# Spring2020V1_1.net
KiCad netlist of a schematic drawn in EAGLE
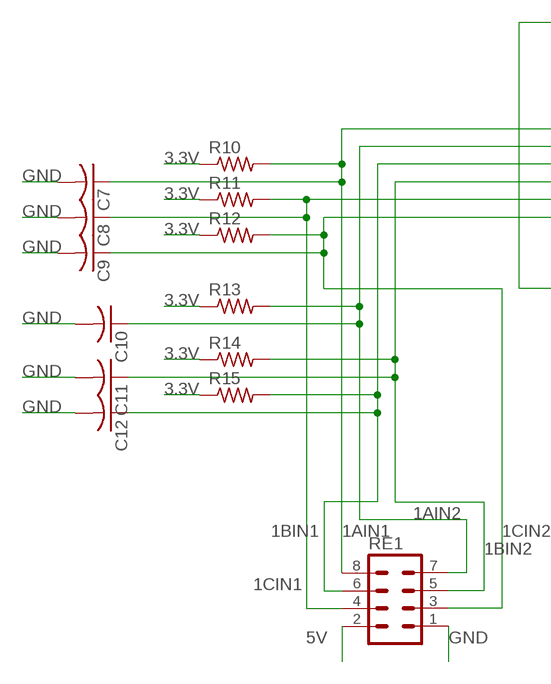
[diagram p0: schematic, sheet 1, part 1 of 2]
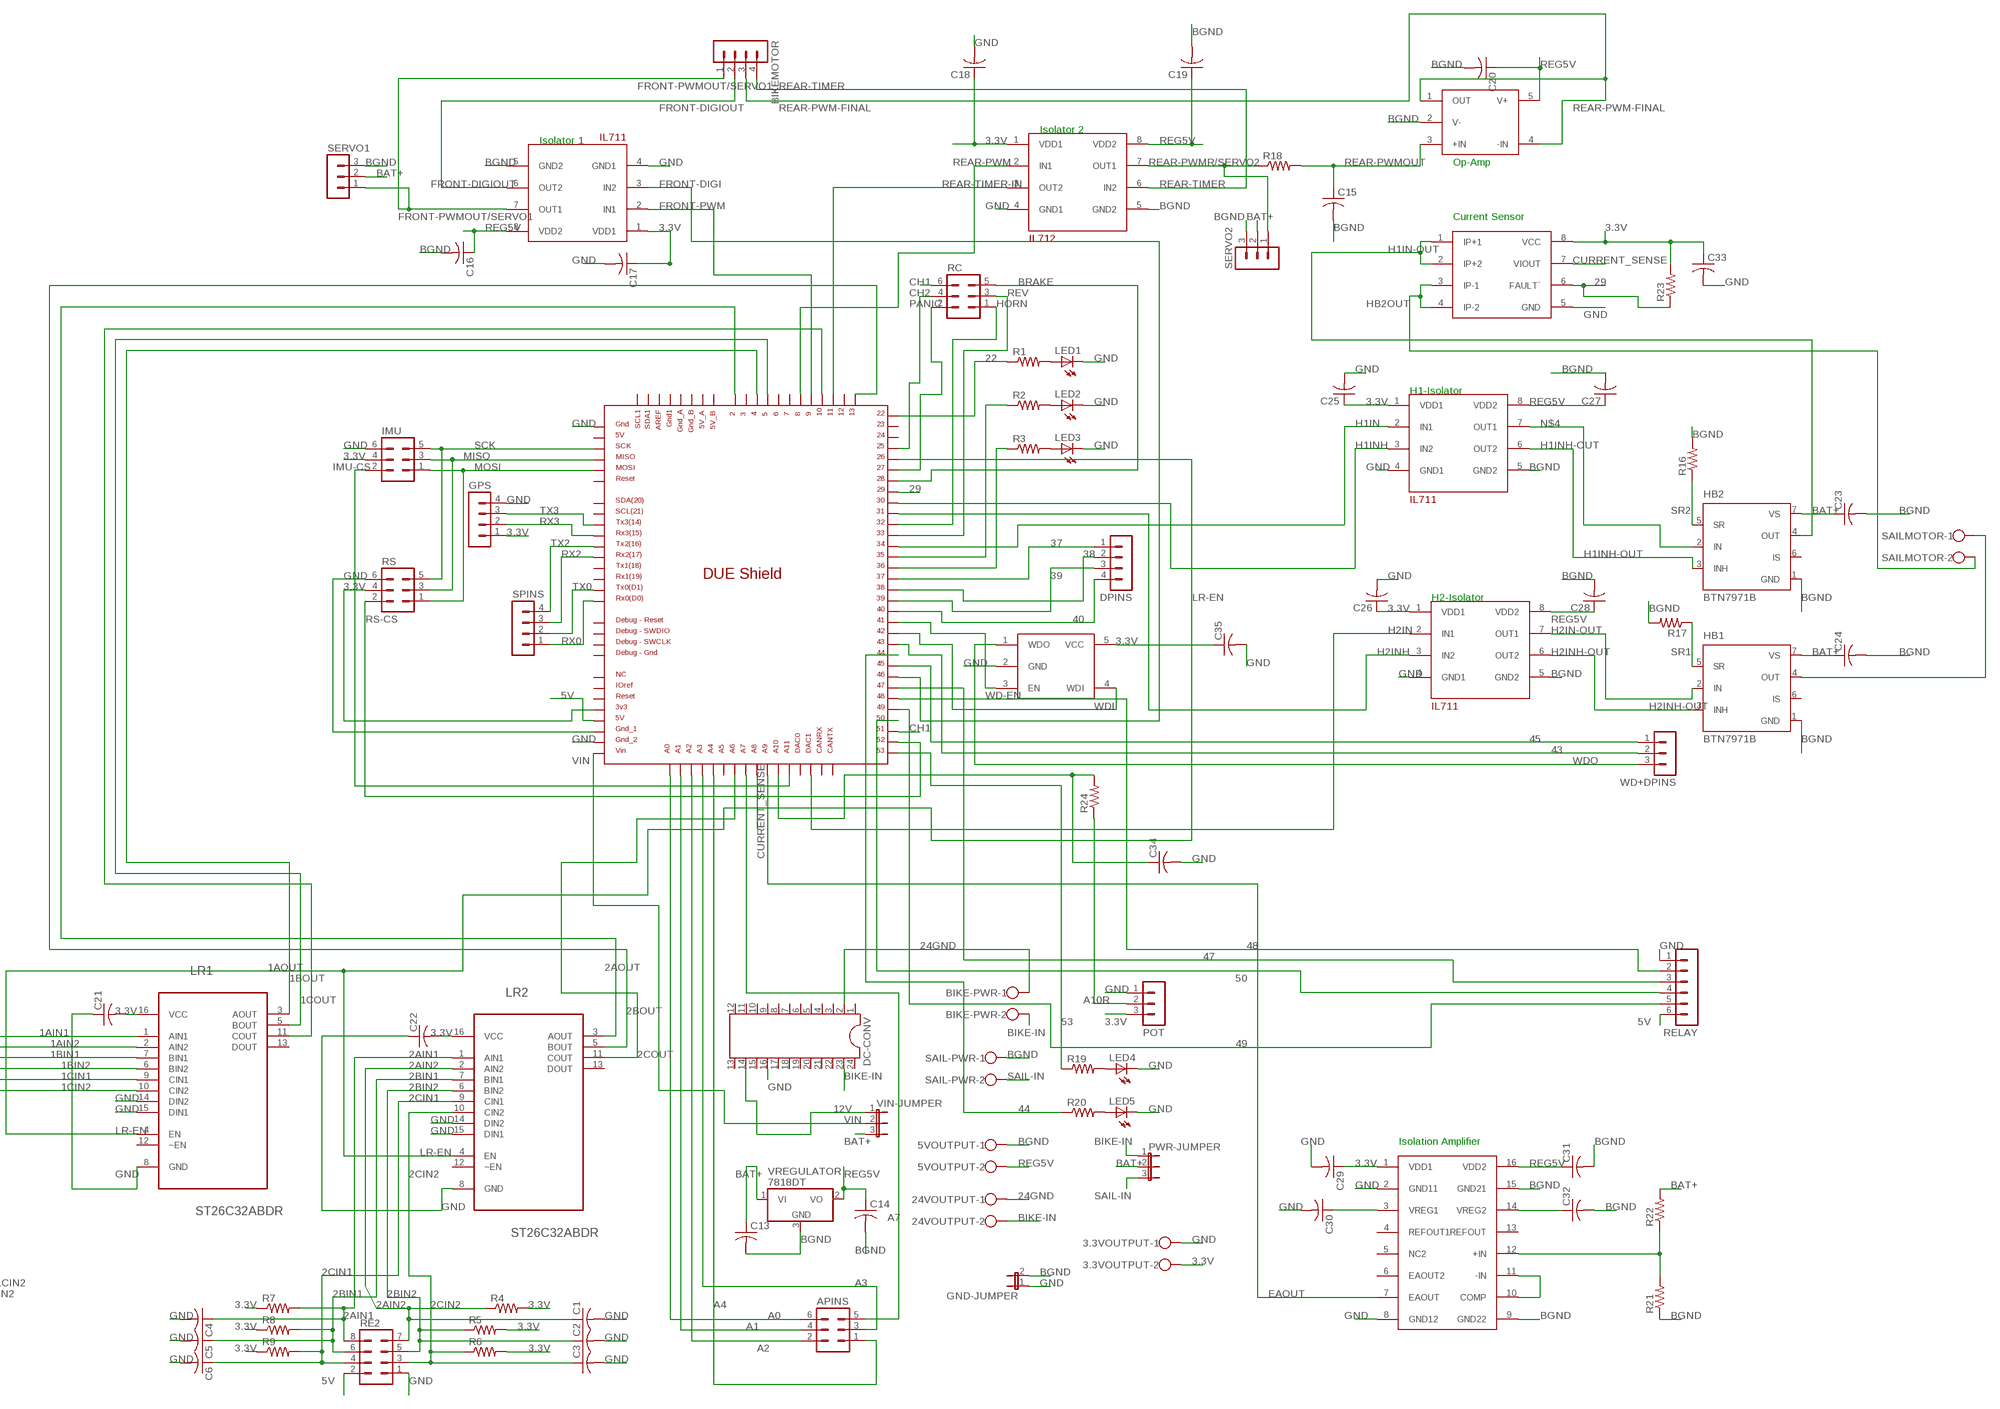
[diagram p1: schematic, sheet 1, part 2 of 2]

(export (version "E")
  (design (tool "Eeschema 10.0.6"))
  (components
    (comp (ref "3.3VOUTPUT")
      (value "W237-102")
      (footprint "eagle-import:W237-102")
      (fields (field (name "MPN") "237-102"))
      (libsource (lib "eagle-import") (part "W237-102"))
    )
    (comp (ref "5VOUTPUT")
      (value "W237-102")
      (footprint "eagle-import:W237-102")
      (fields (field (name "MPN") "237-102"))
      (libsource (lib "eagle-import") (part "W237-102"))
    )
    (comp (ref "24VOUTPUT")
      (value "W237-102")
      (footprint "eagle-import:W237-102")
      (fields (field (name "MPN") "237-102"))
      (libsource (lib "eagle-import") (part "W237-102"))
    )
    (comp (ref "APINS")
      (value "MA03-2")
      (footprint "eagle-import:MA03-2")
      (libsource (lib "eagle-import") (part "MA03-2"))
    )
    (comp (ref "BIKE-PWR")
      (value "W237-102")
      (footprint "eagle-import:W237-102")
      (fields (field (name "MPN") "237-102"))
      (libsource (lib "eagle-import") (part "W237-102"))
    )
    (comp (ref "BIKEMOTOR")
      (value "MA04-1")
      (footprint "eagle-import:MA04-1")
      (libsource (lib "eagle-import") (part "MA04-1"))
    )
    (comp (ref "C1")
      (value "C-US025-025X050")
      (footprint "eagle-import:C025-025X050")
      (libsource (lib "eagle-import") (part "C-US025-025X050"))
    )
    (comp (ref "C2")
      (value "C-US025-025X050")
      (footprint "eagle-import:C025-025X050")
      (libsource (lib "eagle-import") (part "C-US025-025X050"))
    )
    (comp (ref "C3")
      (value "C-US025-025X050")
      (footprint "eagle-import:C025-025X050")
      (libsource (lib "eagle-import") (part "C-US025-025X050"))
    )
    (comp (ref "C4")
      (value "C-US025-025X050")
      (footprint "eagle-import:C025-025X050")
      (libsource (lib "eagle-import") (part "C-US025-025X050"))
    )
    (comp (ref "C5")
      (value "C-US025-025X050")
      (footprint "eagle-import:C025-025X050")
      (libsource (lib "eagle-import") (part "C-US025-025X050"))
    )
    (comp (ref "C6")
      (value "C-US025-025X050")
      (footprint "eagle-import:C025-025X050")
      (libsource (lib "eagle-import") (part "C-US025-025X050"))
    )
    (comp (ref "C7")
      (value "C-US025-025X050")
      (footprint "eagle-import:C025-025X050")
      (libsource (lib "eagle-import") (part "C-US025-025X050"))
    )
    (comp (ref "C8")
      (value "C-US025-025X050")
      (footprint "eagle-import:C025-025X050")
      (libsource (lib "eagle-import") (part "C-US025-025X050"))
    )
    (comp (ref "C9")
      (value "C-US025-025X050")
      (footprint "eagle-import:C025-025X050")
      (libsource (lib "eagle-import") (part "C-US025-025X050"))
    )
    (comp (ref "C10")
      (value "C-US025-025X050")
      (footprint "eagle-import:C025-025X050")
      (libsource (lib "eagle-import") (part "C-US025-025X050"))
    )
    (comp (ref "C11")
      (value "C-US025-025X050")
      (footprint "eagle-import:C025-025X050")
      (libsource (lib "eagle-import") (part "C-US025-025X050"))
    )
    (comp (ref "C12")
      (value "C-US025-025X050")
      (footprint "eagle-import:C025-025X050")
      (libsource (lib "eagle-import") (part "C-US025-025X050"))
    )
    (comp (ref "C13")
      (value "C-US025-050X050")
      (footprint "eagle-import:C025-050X050")
      (libsource (lib "eagle-import") (part "C-US025-050X050"))
    )
    (comp (ref "C14")
      (value "C-US025-050X050")
      (footprint "eagle-import:C025-050X050")
      (libsource (lib "eagle-import") (part "C-US025-050X050"))
    )
    (comp (ref "C15")
      (value "C-US025-050X050")
      (footprint "eagle-import:C025-050X050")
      (libsource (lib "eagle-import") (part "C-US025-050X050"))
    )
    (comp (ref "C16")
      (value "C-US025-050X050")
      (footprint "eagle-import:C025-050X050")
      (libsource (lib "eagle-import") (part "C-US025-050X050"))
    )
    (comp (ref "C17")
      (value "C-US025-050X050")
      (footprint "eagle-import:C025-050X050")
      (libsource (lib "eagle-import") (part "C-US025-050X050"))
    )
    (comp (ref "C18")
      (value "C-US025-050X050")
      (footprint "eagle-import:C025-050X050")
      (libsource (lib "eagle-import") (part "C-US025-050X050"))
    )
    (comp (ref "C19")
      (value "C-US025-050X050")
      (footprint "eagle-import:C025-050X050")
      (libsource (lib "eagle-import") (part "C-US025-050X050"))
    )
    (comp (ref "C20")
      (value "C-US025-050X050")
      (footprint "eagle-import:C025-050X050")
      (libsource (lib "eagle-import") (part "C-US025-050X050"))
    )
    (comp (ref "C21")
      (value "C-US025-050X050")
      (footprint "eagle-import:C025-050X050")
      (libsource (lib "eagle-import") (part "C-US025-050X050"))
    )
    (comp (ref "C22")
      (value "C-US025-050X050")
      (footprint "eagle-import:C025-050X050")
      (libsource (lib "eagle-import") (part "C-US025-050X050"))
    )
    (comp (ref "C23")
      (value "C-US150-091X182")
      (footprint "eagle-import:C150-091X182")
      (libsource (lib "eagle-import") (part "C-US150-091X182"))
    )
    (comp (ref "C24")
      (value "C-US150-091X182")
      (footprint "eagle-import:C150-091X182")
      (libsource (lib "eagle-import") (part "C-US150-091X182"))
    )
    (comp (ref "C25")
      (value "C-US025-050X050")
      (footprint "eagle-import:C025-050X050")
      (libsource (lib "eagle-import") (part "C-US025-050X050"))
    )
    (comp (ref "C26")
      (value "C-US025-050X050")
      (footprint "eagle-import:C025-050X050")
      (libsource (lib "eagle-import") (part "C-US025-050X050"))
    )
    (comp (ref "C27")
      (value "C-US025-050X050")
      (footprint "eagle-import:C025-050X050")
      (libsource (lib "eagle-import") (part "C-US025-050X050"))
    )
    (comp (ref "C28")
      (value "C-US025-050X050")
      (footprint "eagle-import:C025-050X050")
      (libsource (lib "eagle-import") (part "C-US025-050X050"))
    )
    (comp (ref "C29")
      (value "C-US025-050X050")
      (footprint "eagle-import:C025-050X050")
      (libsource (lib "eagle-import") (part "C-US025-050X050"))
    )
    (comp (ref "C30")
      (value "C-US025-050X050")
      (footprint "eagle-import:C025-050X050")
      (libsource (lib "eagle-import") (part "C-US025-050X050"))
    )
    (comp (ref "C31")
      (value "C-US025-050X050")
      (footprint "eagle-import:C025-050X050")
      (libsource (lib "eagle-import") (part "C-US025-050X050"))
    )
    (comp (ref "C32")
      (value "C-US025-050X050")
      (footprint "eagle-import:C025-050X050")
      (libsource (lib "eagle-import") (part "C-US025-050X050"))
    )
    (comp (ref "C33")
      (value "C-US025-050X050")
      (footprint "eagle-import:C025-050X050")
      (libsource (lib "eagle-import") (part "C-US025-050X050"))
    )
    (comp (ref "C34")
      (value "C-US025-050X050")
      (footprint "eagle-import:C025-050X050")
      (libsource (lib "eagle-import") (part "C-US025-050X050"))
    )
    (comp (ref "C35")
      (value "C-US025-025X050")
      (footprint "eagle-import:C025-025X050")
      (libsource (lib "eagle-import") (part "C-US025-025X050"))
    )
    (comp (ref "DC-CONV")
      (value "CU.INC---VAWQ6-Q48-S12H-6")
      (footprint "eagle-import:DIL24-6")
      (libsource (lib "eagle-import") (part "CU.INC---VAWQ6-Q48-S12H-6"))
    )
    (comp (ref "DPINS")
      (value "MA04-1")
      (footprint "eagle-import:MA04-1")
      (libsource (lib "eagle-import") (part "MA04-1"))
    )
    (comp (ref "GND-JUMPER")
      (value "JP1E")
      (footprint "eagle-import:JP1")
      (libsource (lib "eagle-import") (part "JP1E"))
    )
    (comp (ref "GPS")
      (value "MA04-1")
      (footprint "eagle-import:MA04-1")
      (libsource (lib "eagle-import") (part "MA04-1"))
    )
    (comp (ref "HB1")
      (value "BTN7971B")
      (footprint "eagle-import:P-TO263-7-1")
      (libsource (lib "eagle-import") (part "BTN7971B"))
    )
    (comp (ref "HB2")
      (value "BTN7971B")
      (footprint "eagle-import:P-TO263-7-1")
      (libsource (lib "eagle-import") (part "BTN7971B"))
    )
    (comp (ref "IMU")
      (value "MA03-2")
      (footprint "eagle-import:MA03-2")
      (libsource (lib "eagle-import") (part "MA03-2"))
    )
    (comp (ref "LED1")
      (value "LED5MM")
      (footprint "eagle-import:LED5MM")
      (libsource (lib "eagle-import") (part "LED5MM"))
    )
    (comp (ref "LED2")
      (value "LED5MM")
      (footprint "eagle-import:LED5MM")
      (libsource (lib "eagle-import") (part "LED5MM"))
    )
    (comp (ref "LED3")
      (value "LED5MM")
      (footprint "eagle-import:LED5MM")
      (libsource (lib "eagle-import") (part "LED5MM"))
    )
    (comp (ref "LED4")
      (value "LED5MM")
      (footprint "eagle-import:LED5MM")
      (libsource (lib "eagle-import") (part "LED5MM"))
    )
    (comp (ref "LED5")
      (value "LED5MM")
      (footprint "eagle-import:LED5MM")
      (libsource (lib "eagle-import") (part "LED5MM"))
    )
    (comp (ref "LR1")
      (value "ST26C32ABDR")
      (footprint "eagle-import:SOIC127P600X175-16N")
      (libsource (lib "eagle-import") (part "ST26C32ABDR"))
    )
    (comp (ref "LR2")
      (value "ST26C32ABDR")
      (footprint "eagle-import:SOIC127P600X175-16N")
      (libsource (lib "eagle-import") (part "ST26C32ABDR"))
    )
    (comp (ref "OP-AMP")
      (value "OPAMP")
      (footprint "eagle-import:SOT95P280X145-5N")
      (libsource (lib "eagle-import") (part "OPAMP"))
    )
    (comp (ref "POT")
      (value "MA03-1")
      (footprint "eagle-import:MA03-1")
      (libsource (lib "eagle-import") (part "MA03-1"))
    )
    (comp (ref "PWR-JUMPER")
      (value "JP2E")
      (footprint "eagle-import:JP2")
      (libsource (lib "eagle-import") (part "JP2E"))
    )
    (comp (ref "R1")
      (value "R-US_0309/10")
      (footprint "eagle-import:0309_10")
      (libsource (lib "eagle-import") (part "R-US_0309/10"))
    )
    (comp (ref "R2")
      (value "R-US_0309/10")
      (footprint "eagle-import:0309_10")
      (libsource (lib "eagle-import") (part "R-US_0309/10"))
    )
    (comp (ref "R3")
      (value "R-US_0309/10")
      (footprint "eagle-import:0309_10")
      (libsource (lib "eagle-import") (part "R-US_0309/10"))
    )
    (comp (ref "R4")
      (value "R-US_0613/15")
      (footprint "eagle-import:P0613_15")
      (libsource (lib "eagle-import") (part "resistor_R-US_0613/15"))
    )
    (comp (ref "R5")
      (value "R-US_0613/15")
      (footprint "eagle-import:P0613_15")
      (libsource (lib "eagle-import") (part "resistor_R-US_0613/15"))
    )
    (comp (ref "R6")
      (value "R-US_0613/15")
      (footprint "eagle-import:P0613_15")
      (libsource (lib "eagle-import") (part "resistor_R-US_0613/15"))
    )
    (comp (ref "R7")
      (value "R-US_0613/15")
      (footprint "eagle-import:P0613_15")
      (libsource (lib "eagle-import") (part "resistor_R-US_0613/15"))
    )
    (comp (ref "R8")
      (value "R-US_0613/15")
      (footprint "eagle-import:P0613_15")
      (libsource (lib "eagle-import") (part "resistor_R-US_0613/15"))
    )
    (comp (ref "R9")
      (value "R-US_0613/15")
      (footprint "eagle-import:P0613_15")
      (libsource (lib "eagle-import") (part "resistor_R-US_0613/15"))
    )
    (comp (ref "R10")
      (value "R-US_0613/15")
      (footprint "eagle-import:P0613_15")
      (libsource (lib "eagle-import") (part "resistor_R-US_0613/15"))
    )
    (comp (ref "R11")
      (value "R-US_0613/15")
      (footprint "eagle-import:P0613_15")
      (libsource (lib "eagle-import") (part "resistor_R-US_0613/15"))
    )
    (comp (ref "R12")
      (value "R-US_0613/15")
      (footprint "eagle-import:P0613_15")
      (libsource (lib "eagle-import") (part "resistor_R-US_0613/15"))
    )
    (comp (ref "R13")
      (value "R-US_0613/15")
      (footprint "eagle-import:P0613_15")
      (libsource (lib "eagle-import") (part "resistor_R-US_0613/15"))
    )
    (comp (ref "R14")
      (value "R-US_0613/15")
      (footprint "eagle-import:P0613_15")
      (libsource (lib "eagle-import") (part "resistor_R-US_0613/15"))
    )
    (comp (ref "R15")
      (value "R-US_0613/15")
      (footprint "eagle-import:P0613_15")
      (libsource (lib "eagle-import") (part "resistor_R-US_0613/15"))
    )
    (comp (ref "R16")
      (value "R-US_0613/15")
      (footprint "eagle-import:P0613_15")
      (libsource (lib "eagle-import") (part "resistor_R-US_0613/15"))
    )
    (comp (ref "R17")
      (value "R-US_0613/15")
      (footprint "eagle-import:P0613_15")
      (libsource (lib "eagle-import") (part "resistor_R-US_0613/15"))
    )
    (comp (ref "R18")
      (value "R-US_0414/15")
      (footprint "eagle-import:0414_15")
      (libsource (lib "eagle-import") (part "resistor_R-US_0414/15"))
    )
    (comp (ref "R19")
      (value "R-US_0309/10")
      (footprint "eagle-import:0309_10")
      (libsource (lib "eagle-import") (part "R-US_0309/10"))
    )
    (comp (ref "R20")
      (value "R-US_0309/10")
      (footprint "eagle-import:0309_10")
      (libsource (lib "eagle-import") (part "R-US_0309/10"))
    )
    (comp (ref "R21")
      (value "R-US_0414/15")
      (footprint "eagle-import:0414_15")
      (libsource (lib "eagle-import") (part "resistor_R-US_0414/15"))
    )
    (comp (ref "R22")
      (value "R-US_0414/15")
      (footprint "eagle-import:0414_15")
      (libsource (lib "eagle-import") (part "resistor_R-US_0414/15"))
    )
    (comp (ref "R23")
      (value "R-US_0414/15")
      (footprint "eagle-import:0414_15")
      (libsource (lib "eagle-import") (part "resistor_R-US_0414/15"))
    )
    (comp (ref "R24")
      (value "R-US_0414/15")
      (footprint "eagle-import:0414_15")
      (libsource (lib "eagle-import") (part "resistor_R-US_0414/15"))
    )
    (comp (ref "RC")
      (value "MA03-2")
      (footprint "eagle-import:MA03-2")
      (libsource (lib "eagle-import") (part "MA03-2"))
    )
    (comp (ref "RE1")
      (value "MA04-2")
      (footprint "eagle-import:MA04-2")
      (libsource (lib "eagle-import") (part "MA04-2"))
    )
    (comp (ref "RE2")
      (value "MA04-2")
      (footprint "eagle-import:MA04-2")
      (libsource (lib "eagle-import") (part "MA04-2"))
    )
    (comp (ref "RELAY")
      (value "MA06-1")
      (footprint "eagle-import:MA06-1")
      (libsource (lib "eagle-import") (part "MA06-1"))
    )
    (comp (ref "RS")
      (value "MA03-2")
      (footprint "eagle-import:MA03-2")
      (libsource (lib "eagle-import") (part "MA03-2"))
    )
    (comp (ref "SAIL-PWR")
      (value "W237-102")
      (footprint "eagle-import:W237-102")
      (fields (field (name "MPN") "237-102"))
      (libsource (lib "eagle-import") (part "W237-102"))
    )
    (comp (ref "SAILMOTOR")
      (value "W237-102")
      (footprint "eagle-import:W237-102")
      (fields (field (name "MPN") "237-102"))
      (libsource (lib "eagle-import") (part "W237-102"))
    )
    (comp (ref "SERVO1")
      (value "MA03-1")
      (footprint "eagle-import:MA03-1")
      (libsource (lib "eagle-import") (part "MA03-1"))
    )
    (comp (ref "SERVO2")
      (value "MA03-1")
      (footprint "eagle-import:MA03-1")
      (libsource (lib "eagle-import") (part "MA03-1"))
    )
    (comp (ref "SPINS")
      (value "MA04-1")
      (footprint "eagle-import:MA04-1")
      (libsource (lib "eagle-import") (part "MA04-1"))
    )
    (comp (ref "U$1")
      (value "DUE(NORMAL)")
      (footprint "eagle-import:DUE(NORMAL)")
      (libsource (lib "eagle-import") (part "DUE(NORMAL)"))
    )
    (comp (ref "U$2")
      (value "IL-711")
      (footprint "eagle-import:8PINSOIC")
      (libsource (lib "eagle-import") (part "IL-711"))
    )
    (comp (ref "U$3")
      (value "IL-711")
      (footprint "eagle-import:8PINSOIC")
      (libsource (lib "eagle-import") (part "IL-711"))
    )
    (comp (ref "U$4")
      (value "WATCHDOG")
      (footprint "eagle-import:SOT95P280X145-5N")
      (libsource (lib "eagle-import") (part "WATCHDOG"))
    )
    (comp (ref "U$5")
      (value "ISOLATED_ERROR_AMP_ADUM3190")
      (footprint "eagle-import:QSOP16")
      (libsource (lib "eagle-import") (part "ISOLATED_ERROR_AMP_ADUM3190"))
    )
    (comp (ref "U$6")
      (value "IL-711")
      (footprint "eagle-import:8PINSOIC")
      (libsource (lib "eagle-import") (part "IL-711"))
    )
    (comp (ref "U$7")
      (value "IL-712")
      (footprint "eagle-import:8PINSOIC")
      (libsource (lib "eagle-import") (part "IL-712"))
    )
    (comp (ref "U$8")
      (value "LINEAR_CURRENT_SENSOR_ACS711")
      (footprint "eagle-import:SO8")
      (libsource (lib "eagle-import") (part "LINEAR_CURRENT_SENSOR_ACS711"))
    )
    (comp (ref "VIN-JUMPER")
      (value "JP2E")
      (footprint "eagle-import:JP2")
      (libsource (lib "eagle-import") (part "JP2E"))
    )
    (comp (ref "VREGULATOR")
      (value "7818DT")
      (footprint "eagle-import:TO252")
      (libsource (lib "eagle-import") (part "78DT18"))
    )
    (comp (ref "WD+DPINS")
      (value "MA03-1")
      (footprint "eagle-import:MA03-1")
      (libsource (lib "eagle-import") (part "MA03-1"))
    )
  )
  (nets
    (net (code "1") (name "/1AIN1") (class "Default")
      (node (ref "C7") (pin "1") (pinfunction "1_1") (pintype "passive"))
      (node (ref "LR1") (pin "1") (pinfunction "AIN1_1") (pintype "input"))
      (node (ref "R10") (pin "2") (pinfunction "2_2") (pintype "passive"))
      (node (ref "RE1") (pin "8") (pinfunction "8_8") (pintype "passive"))
    )
    (net (code "2") (name "/1AIN2") (class "Default")
      (node (ref "C10") (pin "1") (pinfunction "1_1") (pintype "passive"))
      (node (ref "LR1") (pin "2") (pinfunction "AIN2_2") (pintype "input"))
      (node (ref "R13") (pin "2") (pinfunction "2_2") (pintype "passive"))
      (node (ref "RE1") (pin "7") (pinfunction "7_7") (pintype "passive"))
    )
    (net (code "3") (name "/1AOUT") (class "Default")
      (node (ref "LR1") (pin "3") (pinfunction "AOUT_3") (pintype "output"))
      (node (ref "U$1") (pin "4") (pinfunction "4_4") (pintype "bidirectional"))
    )
    (net (code "4") (name "/1BIN1") (class "Default")
      (node (ref "C12") (pin "1") (pinfunction "1_1") (pintype "passive"))
      (node (ref "LR1") (pin "7") (pinfunction "BIN1_7") (pintype "input"))
      (node (ref "R15") (pin "2") (pinfunction "2_2") (pintype "passive"))
      (node (ref "RE1") (pin "6") (pinfunction "6_6") (pintype "passive"))
    )
    (net (code "5") (name "/1BIN2") (class "Default")
      (node (ref "C11") (pin "1") (pinfunction "1_1") (pintype "passive"))
      (node (ref "LR1") (pin "6") (pinfunction "BIN2_6") (pintype "input"))
      (node (ref "R14") (pin "2") (pinfunction "2_2") (pintype "passive"))
      (node (ref "RE1") (pin "5") (pinfunction "5_5") (pintype "passive"))
    )
    (net (code "6") (name "/1BOUT") (class "Default")
      (node (ref "LR1") (pin "5") (pinfunction "BOUT_5") (pintype "output"))
      (node (ref "U$1") (pin "5") (pinfunction "5_5") (pintype "bidirectional"))
    )
    (net (code "7") (name "/1CIN1") (class "Default")
      (node (ref "C8") (pin "1") (pinfunction "1_1") (pintype "passive"))
      (node (ref "LR1") (pin "9") (pinfunction "CIN1_9") (pintype "input"))
      (node (ref "R11") (pin "2") (pinfunction "2_2") (pintype "passive"))
      (node (ref "RE1") (pin "4") (pinfunction "4_4") (pintype "passive"))
    )
    (net (code "8") (name "/1CIN2") (class "Default")
      (node (ref "C9") (pin "1") (pinfunction "1_1") (pintype "passive"))
      (node (ref "LR1") (pin "10") (pinfunction "CIN2_10") (pintype "input"))
      (node (ref "R12") (pin "2") (pinfunction "2_2") (pintype "passive"))
      (node (ref "RE1") (pin "3") (pinfunction "3_3") (pintype "passive"))
    )
    (net (code "9") (name "/1COUT") (class "Default")
      (node (ref "LR1") (pin "11") (pinfunction "COUT_11") (pintype "output"))
      (node (ref "U$1") (pin "10") (pinfunction "10_10") (pintype "bidirectional"))
    )
    (net (code "10") (name "/2AIN1") (class "Default")
      (node (ref "C4") (pin "1") (pinfunction "1_1") (pintype "passive"))
      (node (ref "LR2") (pin "1") (pinfunction "AIN1_1") (pintype "input"))
      (node (ref "R7") (pin "2") (pinfunction "2_2") (pintype "passive"))
      (node (ref "RE2") (pin "8") (pinfunction "8_8") (pintype "passive"))
    )
    (net (code "11") (name "/2AIN2") (class "Default")
      (node (ref "C1") (pin "1") (pinfunction "1_1") (pintype "passive"))
      (node (ref "LR2") (pin "2") (pinfunction "AIN2_2") (pintype "input"))
      (node (ref "R4") (pin "1") (pinfunction "1_1") (pintype "passive"))
      (node (ref "RE2") (pin "7") (pinfunction "7_7") (pintype "passive"))
    )
    (net (code "12") (name "/2AOUT") (class "Default")
      (node (ref "LR2") (pin "3") (pinfunction "AOUT_3") (pintype "output"))
      (node (ref "U$1") (pin "2") (pinfunction "2_2") (pintype "bidirectional"))
    )
    (net (code "13") (name "/2BIN1") (class "Default")
      (node (ref "C5") (pin "1") (pinfunction "1_1") (pintype "passive"))
      (node (ref "LR2") (pin "7") (pinfunction "BIN1_7") (pintype "input"))
      (node (ref "R8") (pin "2") (pinfunction "2_2") (pintype "passive"))
      (node (ref "RE2") (pin "6") (pinfunction "6_6") (pintype "passive"))
    )
    (net (code "14") (name "/2BIN2") (class "Default")
      (node (ref "C2") (pin "1") (pinfunction "1_1") (pintype "passive"))
      (node (ref "LR2") (pin "6") (pinfunction "BIN2_6") (pintype "input"))
      (node (ref "R5") (pin "1") (pinfunction "1_1") (pintype "passive"))
      (node (ref "RE2") (pin "5") (pinfunction "5_5") (pintype "passive"))
    )
    (net (code "15") (name "/2BOUT") (class "Default")
      (node (ref "LR2") (pin "5") (pinfunction "BOUT_5") (pintype "output"))
      (node (ref "U$1") (pin "13") (pinfunction "13_13") (pintype "bidirectional"))
    )
    (net (code "16") (name "/2CIN1") (class "Default")
      (node (ref "C6") (pin "1") (pinfunction "1_1") (pintype "passive"))
      (node (ref "LR2") (pin "9") (pinfunction "CIN1_9") (pintype "input"))
      (node (ref "R9") (pin "2") (pinfunction "2_2") (pintype "passive"))
      (node (ref "RE2") (pin "4") (pinfunction "4_4") (pintype "passive"))
    )
    (net (code "17") (name "/2CIN2") (class "Default")
      (node (ref "C3") (pin "1") (pinfunction "1_1") (pintype "passive"))
      (node (ref "LR2") (pin "10") (pinfunction "CIN2_10") (pintype "input"))
      (node (ref "R6") (pin "1") (pinfunction "1_1") (pintype "passive"))
      (node (ref "RE2") (pin "3") (pinfunction "3_3") (pintype "passive"))
    )
    (net (code "18") (name "/2COUT") (class "Default")
      (node (ref "LR2") (pin "11") (pinfunction "COUT_11") (pintype "output"))
      (node (ref "U$1") (pin "A6") (pinfunction "A6_A6") (pintype "bidirectional"))
    )
    (net (code "19") (name "/3.3V") (class "Default")
      (node (ref "3.3VOUTPUT") (pin "2") (pinfunction "KL_2") (pintype "passive"))
      (node (ref "C17") (pin "1") (pinfunction "1_1") (pintype "passive"))
      (node (ref "C18") (pin "1") (pinfunction "1_1") (pintype "passive"))
      (node (ref "C21") (pin "2") (pinfunction "2_2") (pintype "passive"))
      (node (ref "C22") (pin "2") (pinfunction "2_2") (pintype "passive"))
      (node (ref "C25") (pin "1") (pinfunction "1_1") (pintype "passive"))
      (node (ref "C26") (pin "1") (pinfunction "1_1") (pintype "passive"))
      (node (ref "C29") (pin "1") (pinfunction "1_1") (pintype "passive"))
      (node (ref "C33") (pin "1") (pinfunction "1_1") (pintype "passive"))
      (node (ref "C35") (pin "1") (pinfunction "1_1") (pintype "passive"))
      (node (ref "GPS") (pin "1") (pinfunction "1_1") (pintype "passive"))
      (node (ref "IMU") (pin "4") (pinfunction "4_4") (pintype "passive"))
      (node (ref "LR1") (pin "16") (pinfunction "VCC_16") (pintype "power_in"))
      (node (ref "LR2") (pin "16") (pinfunction "VCC_16") (pintype "power_in"))
      (node (ref "POT") (pin "3") (pinfunction "3_3") (pintype "passive"))
      (node (ref "R10") (pin "1") (pinfunction "1_1") (pintype "passive"))
      (node (ref "R11") (pin "1") (pinfunction "1_1") (pintype "passive"))
      (node (ref "R12") (pin "1") (pinfunction "1_1") (pintype "passive"))
      (node (ref "R13") (pin "1") (pinfunction "1_1") (pintype "passive"))
      (node (ref "R14") (pin "1") (pinfunction "1_1") (pintype "passive"))
      (node (ref "R15") (pin "1") (pinfunction "1_1") (pintype "passive"))
      (node (ref "R23") (pin "2") (pinfunction "2_2") (pintype "passive"))
      (node (ref "R4") (pin "2") (pinfunction "2_2") (pintype "passive"))
      (node (ref "R5") (pin "2") (pinfunction "2_2") (pintype "passive"))
      (node (ref "R6") (pin "2") (pinfunction "2_2") (pintype "passive"))
      (node (ref "R7") (pin "1") (pinfunction "1_1") (pintype "passive"))
      (node (ref "R8") (pin "1") (pinfunction "1_1") (pintype "passive"))
      (node (ref "R9") (pin "1") (pinfunction "1_1") (pintype "passive"))
      (node (ref "RS") (pin "4") (pinfunction "4_4") (pintype "passive"))
      (node (ref "U$1") (pin "3V3") (pinfunction "3V3_3V3") (pintype "bidirectional"))
      (node (ref "U$2") (pin "1") (pinfunction "VDD1_1") (pintype "power_in"))
      (node (ref "U$3") (pin "1") (pinfunction "VDD1_1") (pintype "power_in"))
      (node (ref "U$4") (pin "5") (pinfunction "VCC_5") (pintype "power_in"))
      (node (ref "U$5") (pin "1") (pinfunction "VDD1_1") (pintype "bidirectional"))
      (node (ref "U$6") (pin "1") (pinfunction "VDD1_1") (pintype "power_in"))
      (node (ref "U$7") (pin "1") (pinfunction "VDD1_1") (pintype "power_in"))
      (node (ref "U$8") (pin "8") (pinfunction "VCC_8") (pintype "bidirectional"))
    )
    (net (code "20") (name "/5V") (class "Default")
      (node (ref "RE1") (pin "2") (pinfunction "2_2") (pintype "passive"))
      (node (ref "RE2") (pin "2") (pinfunction "2_2") (pintype "passive"))
      (node (ref "RELAY") (pin "6") (pinfunction "6_6") (pintype "passive"))
      (node (ref "U$1") (pin "5V") (pinfunction "5V_5V") (pintype "bidirectional"))
    )
    (net (code "21") (name "/12V") (class "Default")
      (node (ref "DC-CONV") (pin "14") (pinfunction "14_14") (pintype "passive"))
      (node (ref "VIN-JUMPER") (pin "1") (pinfunction "1_1") (pintype "passive"))
    )
    (net (code "22") (name "/22") (class "Default")
      (node (ref "R1") (pin "1") (pinfunction "1_1") (pintype "passive"))
      (node (ref "U$1") (pin "22") (pinfunction "22_22") (pintype "bidirectional"))
    )
    (net (code "23") (name "/24GND") (class "Default")
      (node (ref "24VOUTPUT") (pin "1") (pinfunction "KL_1") (pintype "passive"))
      (node (ref "BIKE-PWR") (pin "1") (pinfunction "KL_1") (pintype "passive"))
      (node (ref "DC-CONV") (pin "2") (pinfunction "2_2") (pintype "passive"))
    )
    (net (code "24") (name "/29") (class "Default")
      (node (ref "R23") (pin "1") (pinfunction "1_1") (pintype "passive"))
      (node (ref "U$1") (pin "29") (pinfunction "29_29") (pintype "bidirectional"))
      (node (ref "U$8") (pin "6") (pinfunction "FAULT`_6") (pintype "bidirectional"))
    )
    (net (code "25") (name "/37") (class "Default")
      (node (ref "DPINS") (pin "1") (pinfunction "1_1") (pintype "passive"))
      (node (ref "U$1") (pin "37") (pinfunction "37_37") (pintype "bidirectional"))
    )
    (net (code "26") (name "/38") (class "Default")
      (node (ref "DPINS") (pin "2") (pinfunction "2_2") (pintype "passive"))
      (node (ref "U$1") (pin "38") (pinfunction "38_38") (pintype "bidirectional"))
    )
    (net (code "27") (name "/39") (class "Default")
      (node (ref "DPINS") (pin "3") (pinfunction "3_3") (pintype "passive"))
      (node (ref "U$1") (pin "39") (pinfunction "39_39") (pintype "bidirectional"))
    )
    (net (code "28") (name "/40") (class "Default")
      (node (ref "DPINS") (pin "4") (pinfunction "4_4") (pintype "passive"))
      (node (ref "U$1") (pin "40") (pinfunction "40_40") (pintype "bidirectional"))
    )
    (net (code "29") (name "/43") (class "Default")
      (node (ref "U$1") (pin "43") (pinfunction "43_43") (pintype "bidirectional"))
      (node (ref "WD+DPINS") (pin "2") (pinfunction "2_2") (pintype "passive"))
    )
    (net (code "30") (name "/44") (class "Default")
      (node (ref "R20") (pin "1") (pinfunction "1_1") (pintype "passive"))
      (node (ref "U$1") (pin "44") (pinfunction "44_44") (pintype "bidirectional"))
    )
    (net (code "31") (name "/45") (class "Default")
      (node (ref "U$1") (pin "45") (pinfunction "45_45") (pintype "bidirectional"))
      (node (ref "WD+DPINS") (pin "1") (pinfunction "1_1") (pintype "passive"))
    )
    (net (code "32") (name "/47") (class "Default")
      (node (ref "RELAY") (pin "3") (pinfunction "3_3") (pintype "passive"))
      (node (ref "U$1") (pin "47") (pinfunction "47_47") (pintype "bidirectional"))
    )
    (net (code "33") (name "/48") (class "Default")
      (node (ref "RELAY") (pin "2") (pinfunction "2_2") (pintype "passive"))
      (node (ref "U$1") (pin "48") (pinfunction "48_48") (pintype "bidirectional"))
    )
    (net (code "34") (name "/49") (class "Default")
      (node (ref "RELAY") (pin "5") (pinfunction "5_5") (pintype "passive"))
      (node (ref "U$1") (pin "49") (pinfunction "49_49") (pintype "bidirectional"))
    )
    (net (code "35") (name "/50") (class "Default")
      (node (ref "RELAY") (pin "4") (pinfunction "4_4") (pintype "passive"))
      (node (ref "U$1") (pin "50") (pinfunction "50_50") (pintype "bidirectional"))
    )
    (net (code "36") (name "/53") (class "Default")
      (node (ref "R19") (pin "1") (pinfunction "1_1") (pintype "passive"))
      (node (ref "U$1") (pin "53") (pinfunction "53_53") (pintype "bidirectional"))
    )
    (net (code "37") (name "/A0") (class "Default")
      (node (ref "APINS") (pin "6") (pinfunction "6_6") (pintype "passive"))
      (node (ref "U$1") (pin "A0") (pinfunction "A0_A0") (pintype "bidirectional"))
    )
    (net (code "38") (name "/A1") (class "Default")
      (node (ref "APINS") (pin "4") (pinfunction "4_4") (pintype "passive"))
      (node (ref "U$1") (pin "A1") (pinfunction "A1_A1") (pintype "bidirectional"))
    )
    (net (code "39") (name "/A2") (class "Default")
      (node (ref "APINS") (pin "2") (pinfunction "2_2") (pintype "passive"))
      (node (ref "U$1") (pin "A2") (pinfunction "A2_A2") (pintype "bidirectional"))
    )
    (net (code "40") (name "/A3") (class "Default")
      (node (ref "APINS") (pin "3") (pinfunction "3_3") (pintype "passive"))
      (node (ref "U$1") (pin "A3") (pinfunction "A3_A3") (pintype "bidirectional"))
    )
    (net (code "41") (name "/A4") (class "Default")
      (node (ref "APINS") (pin "1") (pinfunction "1_1") (pintype "passive"))
      (node (ref "U$1") (pin "A4") (pinfunction "A4_A4") (pintype "bidirectional"))
    )
    (net (code "42") (name "/A7") (class "Default")
      (node (ref "APINS") (pin "5") (pinfunction "5_5") (pintype "passive"))
      (node (ref "U$1") (pin "A7") (pinfunction "A7_A7") (pintype "bidirectional"))
    )
    (net (code "43") (name "/A10R") (class "Default")
      (node (ref "POT") (pin "2") (pinfunction "2_2") (pintype "passive"))
      (node (ref "R24") (pin "1") (pinfunction "1_1") (pintype "passive"))
    )
    (net (code "44") (name "/BAT+") (class "Default")
      (node (ref "C13") (pin "1") (pinfunction "1_1") (pintype "passive"))
      (node (ref "C23") (pin "1") (pinfunction "1_1") (pintype "passive"))
      (node (ref "C24") (pin "1") (pinfunction "1_1") (pintype "passive"))
      (node (ref "HB1") (pin "7") (pinfunction "VS_7") (pintype "input"))
      (node (ref "HB2") (pin "7") (pinfunction "VS_7") (pintype "input"))
      (node (ref "PWR-JUMPER") (pin "2") (pinfunction "2_2") (pintype "passive"))
      (node (ref "R22") (pin "2") (pinfunction "2_2") (pintype "passive"))
      (node (ref "SERVO1") (pin "2") (pinfunction "2_2") (pintype "passive"))
      (node (ref "SERVO2") (pin "2") (pinfunction "2_2") (pintype "passive"))
      (node (ref "VIN-JUMPER") (pin "3") (pinfunction "3_3") (pintype "passive"))
      (node (ref "VREGULATOR") (pin "1") (pinfunction "VI_1") (pintype "input"))
    )
    (net (code "45") (name "/BGND") (class "Default")
      (node (ref "5VOUTPUT") (pin "1") (pinfunction "KL_1") (pintype "passive"))
      (node (ref "C13") (pin "2") (pinfunction "2_2") (pintype "passive"))
      (node (ref "C14") (pin "2") (pinfunction "2_2") (pintype "passive"))
      (node (ref "C15") (pin "2") (pinfunction "2_2") (pintype "passive"))
      (node (ref "C16") (pin "2") (pinfunction "2_2") (pintype "passive"))
      (node (ref "C19") (pin "2") (pinfunction "2_2") (pintype "passive"))
      (node (ref "C20") (pin "2") (pinfunction "2_2") (pintype "passive"))
      (node (ref "C23") (pin "2") (pinfunction "2_2") (pintype "passive"))
      (node (ref "C24") (pin "2") (pinfunction "2_2") (pintype "passive"))
      (node (ref "C27") (pin "2") (pinfunction "2_2") (pintype "passive"))
      (node (ref "C28") (pin "2") (pinfunction "2_2") (pintype "passive"))
      (node (ref "C31") (pin "2") (pinfunction "2_2") (pintype "passive"))
      (node (ref "C32") (pin "2") (pinfunction "2_2") (pintype "passive"))
      (node (ref "GND-JUMPER") (pin "2") (pinfunction "2_2") (pintype "passive"))
      (node (ref "HB1") (pin "1") (pinfunction "GND_1") (pintype "power_in"))
      (node (ref "HB2") (pin "1") (pinfunction "GND_1") (pintype "power_in"))
      (node (ref "OP-AMP") (pin "2") (pinfunction "V-_2") (pintype "output"))
      (node (ref "R16") (pin "2") (pinfunction "2_2") (pintype "passive"))
      (node (ref "R17") (pin "2") (pinfunction "2_2") (pintype "passive"))
      (node (ref "R21") (pin "1") (pinfunction "1_1") (pintype "passive"))
      (node (ref "SAIL-PWR") (pin "1") (pinfunction "KL_1") (pintype "passive"))
      (node (ref "SERVO1") (pin "3") (pinfunction "3_3") (pintype "passive"))
      (node (ref "SERVO2") (pin "3") (pinfunction "3_3") (pintype "passive"))
      (node (ref "U$2") (pin "5") (pinfunction "GND2_5") (pintype "power_in"))
      (node (ref "U$3") (pin "5") (pinfunction "GND2_5") (pintype "power_in"))
      (node (ref "U$5") (pin "15") (pinfunction "GND21_15") (pintype "bidirectional"))
      (node (ref "U$5") (pin "9") (pinfunction "GND22_9") (pintype "bidirectional"))
      (node (ref "U$6") (pin "5") (pinfunction "GND2_5") (pintype "power_in"))
      (node (ref "U$7") (pin "5") (pinfunction "GND2_5") (pintype "power_in"))
      (node (ref "VREGULATOR") (pin "3") (pinfunction "GND_3") (pintype "passive"))
    )
    (net (code "46") (name "/BIKE-IN") (class "Default")
      (node (ref "24VOUTPUT") (pin "2") (pinfunction "KL_2") (pintype "passive"))
      (node (ref "BIKE-PWR") (pin "2") (pinfunction "KL_2") (pintype "passive"))
      (node (ref "DC-CONV") (pin "23") (pinfunction "23_23") (pintype "passive"))
      (node (ref "PWR-JUMPER") (pin "1") (pinfunction "1_1") (pintype "passive"))
    )
    (net (code "47") (name "/BRAKE") (class "Default")
      (node (ref "RC") (pin "5") (pinfunction "5_5") (pintype "passive"))
      (node (ref "U$1") (pin "28") (pinfunction "28_28") (pintype "bidirectional"))
    )
    (net (code "48") (name "/CH1") (class "Default")
      (node (ref "RC") (pin "6") (pinfunction "6_6") (pintype "passive"))
      (node (ref "U$1") (pin "51") (pinfunction "51_51") (pintype "bidirectional"))
    )
    (net (code "49") (name "/CH2") (class "Default")
      (node (ref "RC") (pin "4") (pinfunction "4_4") (pintype "passive"))
      (node (ref "U$1") (pin "25") (pinfunction "25_25") (pintype "bidirectional"))
    )
    (net (code "50") (name "/CURRENT_SENSE") (class "Default")
      (node (ref "U$1") (pin "A8") (pinfunction "A8_A8") (pintype "bidirectional"))
      (node (ref "U$8") (pin "7") (pinfunction "VIOUT_7") (pintype "bidirectional"))
    )
    (net (code "51") (name "/EAOUT") (class "Default")
      (node (ref "U$1") (pin "A9") (pinfunction "A9_A9") (pintype "bidirectional"))
      (node (ref "U$5") (pin "7") (pinfunction "EAOUT_7") (pintype "bidirectional"))
    )
    (net (code "52") (name "/FRONT-DIGI") (class "Default")
      (node (ref "U$1") (pin "46") (pinfunction "46_46") (pintype "bidirectional"))
      (node (ref "U$2") (pin "3") (pinfunction "IN2_3") (pintype "input"))
    )
    (net (code "53") (name "/FRONT-DIGIOUT") (class "Default")
      (node (ref "BIKEMOTOR") (pin "2") (pinfunction "2_2") (pintype "passive"))
      (node (ref "U$2") (pin "6") (pinfunction "OUT2_6") (pintype "output"))
    )
    (net (code "54") (name "/FRONT-PWM") (class "Default")
      (node (ref "U$1") (pin "9") (pinfunction "9_9") (pintype "bidirectional"))
      (node (ref "U$2") (pin "2") (pinfunction "IN1_2") (pintype "input"))
    )
    (net (code "55") (name "/FRONT-PWMOUT{slash}SERVO1") (class "Default")
      (node (ref "BIKEMOTOR") (pin "1") (pinfunction "1_1") (pintype "passive"))
      (node (ref "SERVO1") (pin "1") (pinfunction "1_1") (pintype "passive"))
      (node (ref "U$2") (pin "7") (pinfunction "OUT1_7") (pintype "output"))
    )
    (net (code "56") (name "/GND") (class "Default")
      (node (ref "3.3VOUTPUT") (pin "1") (pinfunction "KL_1") (pintype "passive"))
      (node (ref "C1") (pin "2") (pinfunction "2_2") (pintype "passive"))
      (node (ref "C10") (pin "2") (pinfunction "2_2") (pintype "passive"))
      (node (ref "C11") (pin "2") (pinfunction "2_2") (pintype "passive"))
      (node (ref "C12") (pin "2") (pinfunction "2_2") (pintype "passive"))
      (node (ref "C17") (pin "2") (pinfunction "2_2") (pintype "passive"))
      (node (ref "C18") (pin "2") (pinfunction "2_2") (pintype "passive"))
      (node (ref "C2") (pin "2") (pinfunction "2_2") (pintype "passive"))
      (node (ref "C21") (pin "1") (pinfunction "1_1") (pintype "passive"))
      (node (ref "C22") (pin "1") (pinfunction "1_1") (pintype "passive"))
      (node (ref "C25") (pin "2") (pinfunction "2_2") (pintype "passive"))
      (node (ref "C26") (pin "2") (pinfunction "2_2") (pintype "passive"))
      (node (ref "C29") (pin "2") (pinfunction "2_2") (pintype "passive"))
      (node (ref "C3") (pin "2") (pinfunction "2_2") (pintype "passive"))
      (node (ref "C30") (pin "2") (pinfunction "2_2") (pintype "passive"))
      (node (ref "C33") (pin "2") (pinfunction "2_2") (pintype "passive"))
      (node (ref "C34") (pin "2") (pinfunction "2_2") (pintype "passive"))
      (node (ref "C35") (pin "2") (pinfunction "2_2") (pintype "passive"))
      (node (ref "C4") (pin "2") (pinfunction "2_2") (pintype "passive"))
      (node (ref "C5") (pin "2") (pinfunction "2_2") (pintype "passive"))
      (node (ref "C6") (pin "2") (pinfunction "2_2") (pintype "passive"))
      (node (ref "C7") (pin "2") (pinfunction "2_2") (pintype "passive"))
      (node (ref "C8") (pin "2") (pinfunction "2_2") (pintype "passive"))
      (node (ref "C9") (pin "2") (pinfunction "2_2") (pintype "passive"))
      (node (ref "DC-CONV") (pin "16") (pinfunction "16_16") (pintype "passive"))
      (node (ref "GND-JUMPER") (pin "1") (pinfunction "1_1") (pintype "passive"))
      (node (ref "GPS") (pin "4") (pinfunction "4_4") (pintype "passive"))
      (node (ref "IMU") (pin "6") (pinfunction "6_6") (pintype "passive"))
      (node (ref "LED1") (pin "K") (pinfunction "C_K") (pintype "passive"))
      (node (ref "LED2") (pin "K") (pinfunction "C_K") (pintype "passive"))
      (node (ref "LED3") (pin "K") (pinfunction "C_K") (pintype "passive"))
      (node (ref "LED4") (pin "K") (pinfunction "C_K") (pintype "passive"))
      (node (ref "LED5") (pin "K") (pinfunction "C_K") (pintype "passive"))
      (node (ref "LR1") (pin "14") (pinfunction "DIN2_14") (pintype "input"))
      (node (ref "LR1") (pin "15") (pinfunction "DIN1_15") (pintype "input"))
      (node (ref "LR1") (pin "8") (pinfunction "GND_8") (pintype "passive"))
      (node (ref "LR2") (pin "14") (pinfunction "DIN2_14") (pintype "input"))
      (node (ref "LR2") (pin "15") (pinfunction "DIN1_15") (pintype "input"))
      (node (ref "LR2") (pin "8") (pinfunction "GND_8") (pintype "passive"))
      (node (ref "POT") (pin "1") (pinfunction "1_1") (pintype "passive"))
      (node (ref "RE1") (pin "1") (pinfunction "1_1") (pintype "passive"))
      (node (ref "RE2") (pin "1") (pinfunction "1_1") (pintype "passive"))
      (node (ref "RELAY") (pin "1") (pinfunction "1_1") (pintype "passive"))
      (node (ref "RS") (pin "6") (pinfunction "6_6") (pintype "passive"))
      (node (ref "U$1") (pin "5V_ICSP") (pinfunction "5V_ICSP_5V_ICSP") (pintype "bidirectional"))
      (node (ref "U$1") (pin "GND_1") (pinfunction "GND_1_GND_1") (pintype "bidirectional"))
      (node (ref "U$1") (pin "GND_2") (pinfunction "GND_2_GND_2") (pintype "bidirectional"))
      (node (ref "U$2") (pin "4") (pinfunction "GND1_4") (pintype "power_in"))
      (node (ref "U$3") (pin "4") (pinfunction "GND1_4") (pintype "power_in"))
      (node (ref "U$4") (pin "2") (pinfunction "GND_2") (pintype "output"))
      (node (ref "U$5") (pin "2") (pinfunction "GND11_2") (pintype "bidirectional"))
      (node (ref "U$5") (pin "8") (pinfunction "GND12_8") (pintype "bidirectional"))
      (node (ref "U$6") (pin "4") (pinfunction "GND1_4") (pintype "power_in"))
      (node (ref "U$7") (pin "4") (pinfunction "GND1_4") (pintype "power_in"))
      (node (ref "U$8") (pin "5") (pinfunction "GND_5") (pintype "bidirectional"))
    )
    (net (code "57") (name "/H1IN") (class "Default")
      (node (ref "U$1") (pin "34") (pinfunction "34_34") (pintype "bidirectional"))
      (node (ref "U$3") (pin "2") (pinfunction "IN1_2") (pintype "input"))
    )
    (net (code "58") (name "/H1IN-OUT") (class "Default")
      (node (ref "HB2") (pin "4") (pinfunction "OUT_4") (pintype "output"))
      (node (ref "U$8") (pin "1") (pinfunction "IP+1_1") (pintype "bidirectional"))
      (node (ref "U$8") (pin "2") (pinfunction "IP+2_2") (pintype "bidirectional"))
    )
    (net (code "59") (name "/H1INH") (class "Default")
      (node (ref "U$1") (pin "30") (pinfunction "30_30") (pintype "bidirectional"))
      (node (ref "U$3") (pin "3") (pinfunction "IN2_3") (pintype "input"))
    )
    (net (code "60") (name "/H1INH-OUT") (class "Default")
      (node (ref "HB2") (pin "3") (pinfunction "INH_3") (pintype "input"))
      (node (ref "U$3") (pin "6") (pinfunction "OUT2_6") (pintype "output"))
    )
    (net (code "61") (name "/H2IN") (class "Default")
      (node (ref "U$1") (pin "DAC1") (pinfunction "DAC1_DAC1") (pintype "bidirectional"))
      (node (ref "U$6") (pin "2") (pinfunction "IN1_2") (pintype "input"))
    )
    (net (code "62") (name "/H2IN-OUT") (class "Default")
      (node (ref "HB1") (pin "2") (pinfunction "IN_2") (pintype "input"))
      (node (ref "U$6") (pin "7") (pinfunction "OUT1_7") (pintype "output"))
    )
    (net (code "63") (name "/H2INH") (class "Default")
      (node (ref "U$1") (pin "31") (pinfunction "31_31") (pintype "bidirectional"))
      (node (ref "U$6") (pin "3") (pinfunction "IN2_3") (pintype "input"))
    )
    (net (code "64") (name "/H2INH-OUT") (class "Default")
      (node (ref "HB1") (pin "3") (pinfunction "INH_3") (pintype "input"))
      (node (ref "U$6") (pin "6") (pinfunction "OUT2_6") (pintype "output"))
    )
    (net (code "65") (name "/HB2OUT") (class "Default")
      (node (ref "SAILMOTOR") (pin "2") (pinfunction "KL_2") (pintype "passive"))
      (node (ref "U$8") (pin "3") (pinfunction "IP-1_3") (pintype "bidirectional"))
      (node (ref "U$8") (pin "4") (pinfunction "IP-2_4") (pintype "bidirectional"))
    )
    (net (code "66") (name "/HORN") (class "Default")
      (node (ref "RC") (pin "1") (pinfunction "1_1") (pintype "passive"))
      (node (ref "U$1") (pin "32") (pinfunction "32_32") (pintype "bidirectional"))
    )
    (net (code "67") (name "/IMU-CS") (class "Default")
      (node (ref "IMU") (pin "2") (pinfunction "2_2") (pintype "passive"))
      (node (ref "U$1") (pin "A11") (pinfunction "A11_A11") (pintype "bidirectional"))
    )
    (net (code "68") (name "/LR-EN") (class "Default")
      (node (ref "LR1") (pin "4") (pinfunction "EN_4") (pintype "input"))
      (node (ref "LR2") (pin "4") (pinfunction "EN_4") (pintype "input"))
      (node (ref "U$1") (pin "26") (pinfunction "26_26") (pintype "bidirectional"))
    )
    (net (code "69") (name "/MISO") (class "Default")
      (node (ref "IMU") (pin "3") (pinfunction "3_3") (pintype "passive"))
      (node (ref "RS") (pin "3") (pinfunction "3_3") (pintype "passive"))
      (node (ref "U$1") (pin "MISO_ICSP") (pinfunction "MISO_ICSP_MISO_ICSP") (pintype "bidirectional"))
    )
    (net (code "70") (name "/MOSI") (class "Default")
      (node (ref "IMU") (pin "1") (pinfunction "1_1") (pintype "passive"))
      (node (ref "RS") (pin "1") (pinfunction "1_1") (pintype "passive"))
      (node (ref "U$1") (pin "MOSI_ICSP") (pinfunction "MOSI_ICSP_MOSI_ICSP") (pintype "bidirectional"))
    )
    (net (code "71") (name "/N$4") (class "Default")
      (node (ref "HB2") (pin "2") (pinfunction "IN_2") (pintype "input"))
      (node (ref "U$3") (pin "7") (pinfunction "OUT1_7") (pintype "output"))
    )
    (net (code "72") (name "/PANIC") (class "Default")
      (node (ref "RC") (pin "2") (pinfunction "2_2") (pintype "passive"))
      (node (ref "U$1") (pin "27") (pinfunction "27_27") (pintype "bidirectional"))
    )
    (net (code "73") (name "/REAR-PWM") (class "Default")
      (node (ref "U$1") (pin "8") (pinfunction "8_8") (pintype "bidirectional"))
      (node (ref "U$7") (pin "2") (pinfunction "IN1_2") (pintype "input"))
    )
    (net (code "74") (name "/REAR-PWM-FINAL") (class "Default")
      (node (ref "BIKEMOTOR") (pin "3") (pinfunction "3_3") (pintype "passive"))
      (node (ref "OP-AMP") (pin "1") (pinfunction "OUT_1") (pintype "output"))
      (node (ref "OP-AMP") (pin "4") (pinfunction "-IN_4") (pintype "input"))
    )
    (net (code "75") (name "/REAR-PWMOUT") (class "Default")
      (node (ref "C15") (pin "1") (pinfunction "1_1") (pintype "passive"))
      (node (ref "OP-AMP") (pin "3") (pinfunction "+IN_3") (pintype "input"))
      (node (ref "R18") (pin "2") (pinfunction "2_2") (pintype "passive"))
    )
    (net (code "76") (name "/REAR-PWMR{slash}SERVO2") (class "Default")
      (node (ref "R18") (pin "1") (pinfunction "1_1") (pintype "passive"))
      (node (ref "SERVO2") (pin "1") (pinfunction "1_1") (pintype "passive"))
      (node (ref "U$7") (pin "7") (pinfunction "OUT1_7") (pintype "output"))
    )
    (net (code "77") (name "/REAR-TIMER") (class "Default")
      (node (ref "BIKEMOTOR") (pin "4") (pinfunction "4_4") (pintype "passive"))
      (node (ref "U$7") (pin "6") (pinfunction "IN2_6") (pintype "input"))
    )
    (net (code "78") (name "/REAR-TIMER-IN") (class "Default")
      (node (ref "U$1") (pin "11") (pinfunction "11_11") (pintype "bidirectional"))
      (node (ref "U$7") (pin "3") (pinfunction "OUT2_3") (pintype "output"))
    )
    (net (code "79") (name "/REG5V") (class "Default")
      (node (ref "5VOUTPUT") (pin "2") (pinfunction "KL_2") (pintype "passive"))
      (node (ref "C14") (pin "1") (pinfunction "1_1") (pintype "passive"))
      (node (ref "C16") (pin "1") (pinfunction "1_1") (pintype "passive"))
      (node (ref "C19") (pin "1") (pinfunction "1_1") (pintype "passive"))
      (node (ref "C20") (pin "1") (pinfunction "1_1") (pintype "passive"))
      (node (ref "C27") (pin "1") (pinfunction "1_1") (pintype "passive"))
      (node (ref "C28") (pin "1") (pinfunction "1_1") (pintype "passive"))
      (node (ref "C31") (pin "1") (pinfunction "1_1") (pintype "passive"))
      (node (ref "OP-AMP") (pin "5") (pinfunction "V+_5") (pintype "power_in"))
      (node (ref "U$2") (pin "8") (pinfunction "VDD2_8") (pintype "power_in"))
      (node (ref "U$3") (pin "8") (pinfunction "VDD2_8") (pintype "power_in"))
      (node (ref "U$5") (pin "16") (pinfunction "VDD2_16") (pintype "bidirectional"))
      (node (ref "U$6") (pin "8") (pinfunction "VDD2_8") (pintype "power_in"))
      (node (ref "U$7") (pin "8") (pinfunction "VDD2_8") (pintype "power_in"))
      (node (ref "VREGULATOR") (pin "2") (pinfunction "VO_2") (pintype "passive"))
    )
    (net (code "80") (name "/REV") (class "Default")
      (node (ref "RC") (pin "3") (pinfunction "3_3") (pintype "passive"))
      (node (ref "U$1") (pin "33") (pinfunction "33_33") (pintype "bidirectional"))
    )
    (net (code "81") (name "/RS-CS") (class "Default")
      (node (ref "RS") (pin "2") (pinfunction "2_2") (pintype "passive"))
      (node (ref "U$1") (pin "52") (pinfunction "52_52") (pintype "bidirectional"))
    )
    (net (code "82") (name "/RX0") (class "Default")
      (node (ref "SPINS") (pin "1") (pinfunction "1_1") (pintype "passive"))
      (node (ref "U$1") (pin "RX0") (pinfunction "RX0_RX0") (pintype "bidirectional"))
    )
    (net (code "83") (name "/RX2") (class "Default")
      (node (ref "SPINS") (pin "3") (pinfunction "3_3") (pintype "passive"))
      (node (ref "U$1") (pin "RX2") (pinfunction "RX2_RX2") (pintype "bidirectional"))
    )
    (net (code "84") (name "/RX3") (class "Default")
      (node (ref "GPS") (pin "2") (pinfunction "2_2") (pintype "passive"))
      (node (ref "U$1") (pin "RX3") (pinfunction "RX3_RX3") (pintype "bidirectional"))
    )
    (net (code "85") (name "/SAIL-IN") (class "Default")
      (node (ref "PWR-JUMPER") (pin "3") (pinfunction "3_3") (pintype "passive"))
      (node (ref "SAIL-PWR") (pin "2") (pinfunction "KL_2") (pintype "passive"))
    )
    (net (code "86") (name "/SCK") (class "Default")
      (node (ref "IMU") (pin "5") (pinfunction "5_5") (pintype "passive"))
      (node (ref "RS") (pin "5") (pinfunction "5_5") (pintype "passive"))
      (node (ref "U$1") (pin "SCK_ICSP") (pinfunction "SCK_ICSP_SCK_ICSP") (pintype "bidirectional"))
    )
    (net (code "87") (name "/SR1") (class "Default")
      (node (ref "HB1") (pin "5") (pinfunction "SR_5") (pintype "open_collector"))
      (node (ref "R17") (pin "1") (pinfunction "1_1") (pintype "passive"))
    )
    (net (code "88") (name "/SR2") (class "Default")
      (node (ref "HB2") (pin "5") (pinfunction "SR_5") (pintype "open_collector"))
      (node (ref "R16") (pin "1") (pinfunction "1_1") (pintype "passive"))
    )
    (net (code "89") (name "/TX0") (class "Default")
      (node (ref "SPINS") (pin "2") (pinfunction "2_2") (pintype "passive"))
      (node (ref "U$1") (pin "TX0") (pinfunction "TX0_TX0") (pintype "bidirectional"))
    )
    (net (code "90") (name "/TX2") (class "Default")
      (node (ref "SPINS") (pin "4") (pinfunction "4_4") (pintype "passive"))
      (node (ref "U$1") (pin "TX2") (pinfunction "TX2_TX2") (pintype "bidirectional"))
    )
    (net (code "91") (name "/TX3") (class "Default")
      (node (ref "GPS") (pin "3") (pinfunction "3_3") (pintype "passive"))
      (node (ref "U$1") (pin "TX3") (pinfunction "TX3_TX3") (pintype "bidirectional"))
    )
    (net (code "92") (name "/VIN") (class "Default")
      (node (ref "U$1") (pin "VIN") (pinfunction "VIN_VIN") (pintype "bidirectional"))
      (node (ref "VIN-JUMPER") (pin "2") (pinfunction "2_2") (pintype "passive"))
    )
    (net (code "93") (name "/WD-EN") (class "Default")
      (node (ref "U$1") (pin "41") (pinfunction "41_41") (pintype "bidirectional"))
      (node (ref "U$4") (pin "3") (pinfunction "EN_3") (pintype "input"))
    )
    (net (code "94") (name "/WDI") (class "Default")
      (node (ref "U$1") (pin "42") (pinfunction "42_42") (pintype "bidirectional"))
      (node (ref "U$4") (pin "4") (pinfunction "WDI_4") (pintype "input"))
    )
    (net (code "95") (name "/WDO") (class "Default")
      (node (ref "U$4") (pin "1") (pinfunction "WDO_1") (pintype "output"))
      (node (ref "WD+DPINS") (pin "3") (pinfunction "3_3") (pintype "passive"))
    )
    (net (code "96") (name "Net-(C34-Pad1)") (class "Default")
      (node (ref "C34") (pin "1") (pinfunction "1_1") (pintype "passive"))
      (node (ref "R24") (pin "2") (pinfunction "2_2") (pintype "passive"))
      (node (ref "U$1") (pin "A10") (pinfunction "A10_A10") (pintype "bidirectional"))
    )
    (net (code "97") (name "Net-(HB1-OUT)") (class "Default")
      (node (ref "HB1") (pin "4") (pinfunction "OUT_4") (pintype "output"))
      (node (ref "SAILMOTOR") (pin "1") (pinfunction "KL_1") (pintype "passive"))
    )
    (net (code "98") (name "Net-(LED1-PadA)") (class "Default")
      (node (ref "LED1") (pin "A") (pinfunction "A_A") (pintype "passive"))
      (node (ref "R1") (pin "2") (pinfunction "2_2") (pintype "passive"))
    )
    (net (code "99") (name "Net-(LED2-PadA)") (class "Default")
      (node (ref "LED2") (pin "A") (pinfunction "A_A") (pintype "passive"))
      (node (ref "R2") (pin "2") (pinfunction "2_2") (pintype "passive"))
    )
    (net (code "100") (name "Net-(LED3-PadA)") (class "Default")
      (node (ref "LED3") (pin "A") (pinfunction "A_A") (pintype "passive"))
      (node (ref "R3") (pin "2") (pinfunction "2_2") (pintype "passive"))
    )
    (net (code "101") (name "Net-(LED4-PadA)") (class "Default")
      (node (ref "LED4") (pin "A") (pinfunction "A_A") (pintype "passive"))
      (node (ref "R19") (pin "2") (pinfunction "2_2") (pintype "passive"))
    )
    (net (code "102") (name "Net-(LED5-PadA)") (class "Default")
      (node (ref "LED5") (pin "A") (pinfunction "A_A") (pintype "passive"))
      (node (ref "R20") (pin "2") (pinfunction "2_2") (pintype "passive"))
    )
    (net (code "103") (name "Net-(R2-Pad1)") (class "Default")
      (node (ref "R2") (pin "1") (pinfunction "1_1") (pintype "passive"))
      (node (ref "U$1") (pin "35") (pinfunction "35_35") (pintype "bidirectional"))
    )
    (net (code "104") (name "Net-(R3-Pad1)") (class "Default")
      (node (ref "R3") (pin "1") (pinfunction "1_1") (pintype "passive"))
      (node (ref "U$1") (pin "36") (pinfunction "36_36") (pintype "bidirectional"))
    )
    (net (code "105") (name "Net-(U$5-+IN)") (class "Default")
      (node (ref "R21") (pin "2") (pinfunction "2_2") (pintype "passive"))
      (node (ref "R22") (pin "1") (pinfunction "1_1") (pintype "passive"))
      (node (ref "U$5") (pin "12") (pinfunction "+IN_12") (pintype "bidirectional"))
    )
    (net (code "106") (name "Net-(U$5--IN)") (class "Default")
      (node (ref "U$5") (pin "10") (pinfunction "COMP_10") (pintype "bidirectional"))
      (node (ref "U$5") (pin "11") (pinfunction "-IN_11") (pintype "bidirectional"))
    )
    (net (code "107") (name "Net-(U$5-VREG1)") (class "Default")
      (node (ref "C30") (pin "1") (pinfunction "1_1") (pintype "passive"))
      (node (ref "U$5") (pin "3") (pinfunction "VREG1_3") (pintype "bidirectional"))
    )
    (net (code "108") (name "Net-(U$5-VREG2)") (class "Default")
      (node (ref "C32") (pin "1") (pinfunction "1_1") (pintype "passive"))
      (node (ref "U$5") (pin "14") (pinfunction "VREG2_14") (pintype "bidirectional"))
    )
    (net (code "109") (name "unconnected-(DC-CONV-Pad1)") (class "Default")
      (node (ref "DC-CONV") (pin "1") (pinfunction "1_1") (pintype "passive"))
    )
    (net (code "110") (name "unconnected-(DC-CONV-Pad3)") (class "Default")
      (node (ref "DC-CONV") (pin "3") (pinfunction "3_3") (pintype "passive"))
    )
    (net (code "111") (name "unconnected-(DC-CONV-Pad4)") (class "Default")
      (node (ref "DC-CONV") (pin "4") (pinfunction "4_4") (pintype "passive"))
    )
    (net (code "112") (name "unconnected-(DC-CONV-Pad5)") (class "Default")
      (node (ref "DC-CONV") (pin "5") (pinfunction "5_5") (pintype "passive"))
    )
    (net (code "113") (name "unconnected-(DC-CONV-Pad6)") (class "Default")
      (node (ref "DC-CONV") (pin "6") (pinfunction "6_6") (pintype "passive"))
    )
    (net (code "114") (name "unconnected-(DC-CONV-Pad7)") (class "Default")
      (node (ref "DC-CONV") (pin "7") (pinfunction "7_7") (pintype "passive"))
    )
    (net (code "115") (name "unconnected-(DC-CONV-Pad8)") (class "Default")
      (node (ref "DC-CONV") (pin "8") (pinfunction "8_8") (pintype "passive"))
    )
    (net (code "116") (name "unconnected-(DC-CONV-Pad9)") (class "Default")
      (node (ref "DC-CONV") (pin "9") (pinfunction "9_9") (pintype "passive"))
    )
    (net (code "117") (name "unconnected-(DC-CONV-Pad10)") (class "Default")
      (node (ref "DC-CONV") (pin "10") (pinfunction "10_10") (pintype "passive"))
    )
    (net (code "118") (name "unconnected-(DC-CONV-Pad11)") (class "Default")
      (node (ref "DC-CONV") (pin "11") (pinfunction "11_11") (pintype "passive"))
    )
    (net (code "119") (name "unconnected-(DC-CONV-Pad12)") (class "Default")
      (node (ref "DC-CONV") (pin "12") (pinfunction "12_12") (pintype "passive"))
    )
    (net (code "120") (name "unconnected-(DC-CONV-Pad13)") (class "Default")
      (node (ref "DC-CONV") (pin "13") (pinfunction "13_13") (pintype "passive"))
    )
    (net (code "121") (name "unconnected-(DC-CONV-Pad15)") (class "Default")
      (node (ref "DC-CONV") (pin "15") (pinfunction "15_15") (pintype "passive"))
    )
    (net (code "122") (name "unconnected-(DC-CONV-Pad17)") (class "Default")
      (node (ref "DC-CONV") (pin "17") (pinfunction "17_17") (pintype "passive"))
    )
    (net (code "123") (name "unconnected-(DC-CONV-Pad18)") (class "Default")
      (node (ref "DC-CONV") (pin "18") (pinfunction "18_18") (pintype "passive"))
    )
    (net (code "124") (name "unconnected-(DC-CONV-Pad19)") (class "Default")
      (node (ref "DC-CONV") (pin "19") (pinfunction "19_19") (pintype "passive"))
    )
    (net (code "125") (name "unconnected-(DC-CONV-Pad20)") (class "Default")
      (node (ref "DC-CONV") (pin "20") (pinfunction "20_20") (pintype "passive"))
    )
    (net (code "126") (name "unconnected-(DC-CONV-Pad21)") (class "Default")
      (node (ref "DC-CONV") (pin "21") (pinfunction "21_21") (pintype "passive"))
    )
    (net (code "127") (name "unconnected-(DC-CONV-Pad22)") (class "Default")
      (node (ref "DC-CONV") (pin "22") (pinfunction "22_22") (pintype "passive"))
    )
    (net (code "128") (name "unconnected-(DC-CONV-Pad24)") (class "Default")
      (node (ref "DC-CONV") (pin "24") (pinfunction "24_24") (pintype "passive"))
    )
    (net (code "129") (name "unconnected-(HB1-IS-Pad6)") (class "Default")
      (node (ref "HB1") (pin "6") (pinfunction "IS_6") (pintype "output"))
    )
    (net (code "130") (name "unconnected-(HB2-IS-Pad6)") (class "Default")
      (node (ref "HB2") (pin "6") (pinfunction "IS_6") (pintype "output"))
    )
    (net (code "131") (name "unconnected-(LR1-DOUT-Pad13)") (class "Default")
      (node (ref "LR1") (pin "13") (pinfunction "DOUT_13") (pintype "output"))
    )
    (net (code "132") (name "unconnected-(LR1-~{EN}-Pad12)") (class "Default")
      (node (ref "LR1") (pin "12") (pinfunction "~{EN}_12") (pintype "input"))
    )
    (net (code "133") (name "unconnected-(LR2-DOUT-Pad13)") (class "Default")
      (node (ref "LR2") (pin "13") (pinfunction "DOUT_13") (pintype "output"))
    )
    (net (code "134") (name "unconnected-(LR2-~{EN}-Pad12)") (class "Default")
      (node (ref "LR2") (pin "12") (pinfunction "~{EN}_12") (pintype "input"))
    )
    (net (code "135") (name "unconnected-(U$1-Pad3)") (class "Default")
      (node (ref "U$1") (pin "3") (pinfunction "3_3") (pintype "bidirectional"))
    )
    (net (code "136") (name "unconnected-(U$1-Pad5V_A)") (class "Default")
      (node (ref "U$1") (pin "5V_A") (pinfunction "5V_A_5V_A") (pintype "bidirectional"))
    )
    (net (code "137") (name "unconnected-(U$1-Pad5V_B)") (class "Default")
      (node (ref "U$1") (pin "5V_B") (pinfunction "5V_B_5V_B") (pintype "bidirectional"))
    )
    (net (code "138") (name "unconnected-(U$1-Pad6)") (class "Default")
      (node (ref "U$1") (pin "6") (pinfunction "6_6") (pintype "bidirectional"))
    )
    (net (code "139") (name "unconnected-(U$1-Pad7)") (class "Default")
      (node (ref "U$1") (pin "7") (pinfunction "7_7") (pintype "bidirectional"))
    )
    (net (code "140") (name "unconnected-(U$1-Pad12)") (class "Default")
      (node (ref "U$1") (pin "12") (pinfunction "12_12") (pintype "bidirectional"))
    )
    (net (code "141") (name "unconnected-(U$1-Pad23)") (class "Default")
      (node (ref "U$1") (pin "23") (pinfunction "23_23") (pintype "bidirectional"))
    )
    (net (code "142") (name "unconnected-(U$1-Pad24)") (class "Default")
      (node (ref "U$1") (pin "24") (pinfunction "24_24") (pintype "bidirectional"))
    )
    (net (code "143") (name "unconnected-(U$1-PadA5)") (class "Default")
      (node (ref "U$1") (pin "A5") (pinfunction "A5_A5") (pintype "bidirectional"))
    )
    (net (code "144") (name "unconnected-(U$1-PadAREF)") (class "Default")
      (node (ref "U$1") (pin "AREF") (pinfunction "AREF_AREF") (pintype "bidirectional"))
    )
    (net (code "145") (name "unconnected-(U$1-PadCANRX)") (class "Default")
      (node (ref "U$1") (pin "CANRX") (pinfunction "CANRX_CANRX") (pintype "bidirectional"))
    )
    (net (code "146") (name "unconnected-(U$1-PadCANTX)") (class "Default")
      (node (ref "U$1") (pin "CANTX") (pinfunction "CANTX_CANTX") (pintype "bidirectional"))
    )
    (net (code "147") (name "unconnected-(U$1-PadDAC0)") (class "Default")
      (node (ref "U$1") (pin "DAC0") (pinfunction "DAC0_DAC0") (pintype "bidirectional"))
    )
    (net (code "148") (name "unconnected-(U$1-PadGND1)") (class "Default")
      (node (ref "U$1") (pin "GND1") (pinfunction "GND1_GND1") (pintype "bidirectional"))
    )
    (net (code "149") (name "unconnected-(U$1-PadGND_A)") (class "Default")
      (node (ref "U$1") (pin "GND_A") (pinfunction "GND_A_GND_A") (pintype "bidirectional"))
    )
    (net (code "150") (name "unconnected-(U$1-PadGND_B)") (class "Default")
      (node (ref "U$1") (pin "GND_B") (pinfunction "GND_B_GND_B") (pintype "bidirectional"))
    )
    (net (code "151") (name "unconnected-(U$1-PadGND_DEBUG)") (class "Default")
      (node (ref "U$1") (pin "GND_DEBUG") (pinfunction "GND_DEBUG_GND_DEBUG") (pintype "bidirectional"))
    )
    (net (code "152") (name "unconnected-(U$1-PadGND_ICSP)") (class "Default")
      (node (ref "U$1") (pin "GND_ICSP") (pinfunction "GND_ICSP_GND_ICSP") (pintype "bidirectional"))
    )
    (net (code "153") (name "unconnected-(U$1-PadIOREF)") (class "Default")
      (node (ref "U$1") (pin "IOREF") (pinfunction "IOREF_IOREF") (pintype "bidirectional"))
    )
    (net (code "154") (name "unconnected-(U$1-PadNC)") (class "Default")
      (node (ref "U$1") (pin "NC") (pinfunction "NC_NC") (pintype "bidirectional"))
    )
    (net (code "155") (name "unconnected-(U$1-PadRESET)") (class "Default")
      (node (ref "U$1") (pin "RESET") (pinfunction "RESET_RESET") (pintype "bidirectional"))
    )
    (net (code "156") (name "unconnected-(U$1-PadRESET_DEBUG)") (class "Default")
      (node (ref "U$1") (pin "RESET_DEBUG") (pinfunction "RESET_DEBUG_RESET_DEBUG") (pintype "bidirectional"))
    )
    (net (code "157") (name "unconnected-(U$1-PadRESET_ICSP)") (class "Default")
      (node (ref "U$1") (pin "RESET_ICSP") (pinfunction "RESET_ICSP_RESET_ICSP") (pintype "bidirectional"))
    )
    (net (code "158") (name "unconnected-(U$1-PadRX1)") (class "Default")
      (node (ref "U$1") (pin "RX1") (pinfunction "RX1_RX1") (pintype "bidirectional"))
    )
    (net (code "159") (name "unconnected-(U$1-PadSCL)") (class "Default")
      (node (ref "U$1") (pin "SCL") (pinfunction "SCL_SCL") (pintype "bidirectional"))
    )
    (net (code "160") (name "unconnected-(U$1-PadSCL1)") (class "Default")
      (node (ref "U$1") (pin "SCL1") (pinfunction "SCL1_SCL1") (pintype "bidirectional"))
    )
    (net (code "161") (name "unconnected-(U$1-PadSDA)") (class "Default")
      (node (ref "U$1") (pin "SDA") (pinfunction "SDA_SDA") (pintype "bidirectional"))
    )
    (net (code "162") (name "unconnected-(U$1-PadSDA1)") (class "Default")
      (node (ref "U$1") (pin "SDA1") (pinfunction "SDA1_SDA1") (pintype "bidirectional"))
    )
    (net (code "163") (name "unconnected-(U$1-PadSWCLK_DEBUG)") (class "Default")
      (node (ref "U$1") (pin "SWCLK_DEBUG") (pinfunction "SWCLK_DEBUG_SWCLK_DEBUG") (pintype "bidirectional"))
    )
    (net (code "164") (name "unconnected-(U$1-PadSWDIO_DEBUG)") (class "Default")
      (node (ref "U$1") (pin "SWDIO_DEBUG") (pinfunction "SWDIO_DEBUG_SWDIO_DEBUG") (pintype "bidirectional"))
    )
    (net (code "165") (name "unconnected-(U$1-PadTX1)") (class "Default")
      (node (ref "U$1") (pin "TX1") (pinfunction "TX1_TX1") (pintype "bidirectional"))
    )
    (net (code "166") (name "unconnected-(U$5-EAOUT2-Pad6)") (class "Default")
      (node (ref "U$5") (pin "6") (pinfunction "EAOUT2_6") (pintype "bidirectional"))
    )
    (net (code "167") (name "unconnected-(U$5-NC2-Pad5)") (class "Default")
      (node (ref "U$5") (pin "5") (pinfunction "NC2_5") (pintype "bidirectional"))
    )
    (net (code "168") (name "unconnected-(U$5-REFOUT-Pad13)") (class "Default")
      (node (ref "U$5") (pin "13") (pinfunction "REFOUT_13") (pintype "bidirectional"))
    )
    (net (code "169") (name "unconnected-(U$5-REFOUT1-Pad4)") (class "Default")
      (node (ref "U$5") (pin "4") (pinfunction "REFOUT1_4") (pintype "bidirectional"))
    )
  )
)
